# NusbioV2_Board.net
KiCad netlist of a schematic drawn in EAGLE
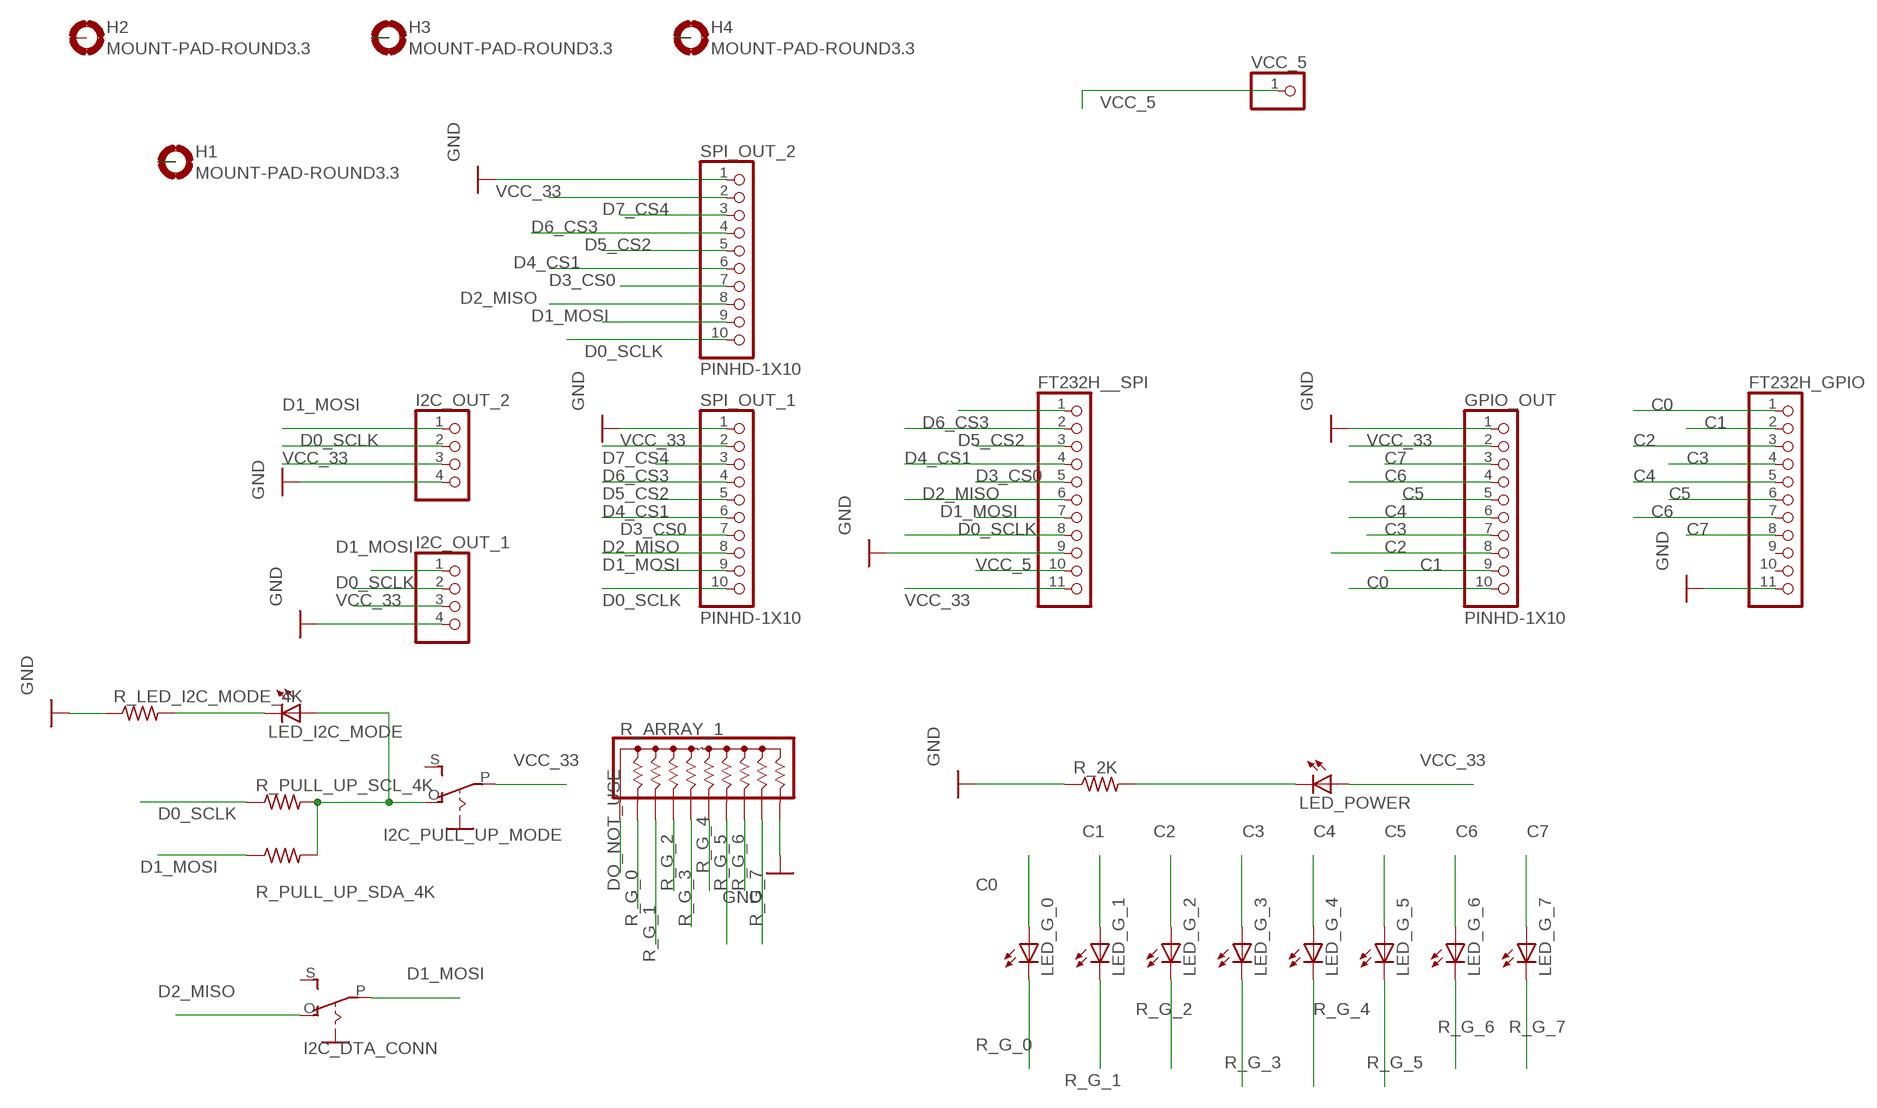
[diagram p0: schematic, sheet 1]

(export (version "E")
  (design (tool "Eeschema 10.0.6"))
  (components
    (comp (ref "FT232H_GPIO")
      (value "PINHD-1X11")
      (footprint "eagle-import:1X11")
      (libsource (lib "eagle-import") (part "PINHD-1X11"))
    )
    (comp (ref "FT232H__SPI")
      (value "PINHD-1X11")
      (footprint "eagle-import:1X11")
      (libsource (lib "eagle-import") (part "PINHD-1X11"))
    )
    (comp (ref "GPIO_OUT")
      (value "PINHD-1X10")
      (footprint "eagle-import:1X10-BIG")
      (libsource (lib "eagle-import") (part "PINHD-1X10"))
    )
    (comp (ref "H1")
      (value "MOUNT-PAD-ROUND3.3")
      (footprint "eagle-import:3,3-PAD")
      (libsource (lib "eagle-import") (part "MOUNT-PAD-ROUND3.3"))
    )
    (comp (ref "H2")
      (value "MOUNT-PAD-ROUND3.3")
      (footprint "eagle-import:3,3-PAD")
      (libsource (lib "eagle-import") (part "MOUNT-PAD-ROUND3.3"))
    )
    (comp (ref "H3")
      (value "MOUNT-PAD-ROUND3.3")
      (footprint "eagle-import:3,3-PAD")
      (libsource (lib "eagle-import") (part "MOUNT-PAD-ROUND3.3"))
    )
    (comp (ref "H4")
      (value "MOUNT-PAD-ROUND3.3")
      (footprint "eagle-import:3,3-PAD")
      (libsource (lib "eagle-import") (part "MOUNT-PAD-ROUND3.3"))
    )
    (comp (ref "I2C_DTA_CONN")
      (value "EG1218S")
      (footprint "eagle-import:EG1218")
      (libsource (lib "eagle-import") (part "EG1218S"))
    )
    (comp (ref "I2C_OUT_1")
      (value "PINHD-1X4")
      (footprint "eagle-import:1X04")
      (libsource (lib "eagle-import") (part "PINHD-1X4"))
    )
    (comp (ref "I2C_OUT_2")
      (value "PINHD-1X4")
      (footprint "eagle-import:1X04")
      (libsource (lib "eagle-import") (part "PINHD-1X4"))
    )
    (comp (ref "I2C_PULL_UP_MODE")
      (value "EG1218S")
      (footprint "eagle-import:EG1218")
      (libsource (lib "eagle-import") (part "EG1218S"))
    )
    (comp (ref "LED_G_0")
      (value "LEDSMT1206")
      (footprint "eagle-import:1206")
      (libsource (lib "eagle-import") (part "LEDSMT1206"))
    )
    (comp (ref "LED_G_1")
      (value "LEDSMT1206")
      (footprint "eagle-import:1206")
      (libsource (lib "eagle-import") (part "LEDSMT1206"))
    )
    (comp (ref "LED_G_2")
      (value "LEDSMT1206")
      (footprint "eagle-import:1206")
      (libsource (lib "eagle-import") (part "LEDSMT1206"))
    )
    (comp (ref "LED_G_3")
      (value "LEDSMT1206")
      (footprint "eagle-import:1206")
      (libsource (lib "eagle-import") (part "LEDSMT1206"))
    )
    (comp (ref "LED_G_4")
      (value "LEDSMT1206")
      (footprint "eagle-import:1206")
      (libsource (lib "eagle-import") (part "LEDSMT1206"))
    )
    (comp (ref "LED_G_5")
      (value "LEDSMT1206")
      (footprint "eagle-import:1206")
      (libsource (lib "eagle-import") (part "LEDSMT1206"))
    )
    (comp (ref "LED_G_6")
      (value "LEDSMT1206")
      (footprint "eagle-import:1206")
      (libsource (lib "eagle-import") (part "LEDSMT1206"))
    )
    (comp (ref "LED_G_7")
      (value "LEDSMT1206")
      (footprint "eagle-import:1206")
      (libsource (lib "eagle-import") (part "LEDSMT1206"))
    )
    (comp (ref "LED_I2C_MODE")
      (value "LEDSMT1206")
      (footprint "eagle-import:1206")
      (libsource (lib "eagle-import") (part "LEDSMT1206"))
    )
    (comp (ref "LED_POWER")
      (value "LEDSMT1206")
      (footprint "eagle-import:1206")
      (libsource (lib "eagle-import") (part "LEDSMT1206"))
    )
    (comp (ref "R_2K")
      (value "R-US_R1206")
      (footprint "eagle-import:R1206")
      (libsource (lib "eagle-import") (part "R-US_R1206"))
    )
    (comp (ref "R_ARRAY_1")
      (value "4610X")
      (footprint "eagle-import:SIP10")
      (libsource (lib "eagle-import") (part "4610X"))
    )
    (comp (ref "R_LED_I2C_MODE_4K")
      (value "R-US_R1206")
      (footprint "eagle-import:R1206")
      (libsource (lib "eagle-import") (part "R-US_R1206"))
    )
    (comp (ref "R_PULL_UP_SCL_4K")
      (value "R-US_R1206")
      (footprint "eagle-import:R1206")
      (libsource (lib "eagle-import") (part "R-US_R1206"))
    )
    (comp (ref "R_PULL_UP_SDA_4K")
      (value "R-US_R1206")
      (footprint "eagle-import:R1206")
      (libsource (lib "eagle-import") (part "R-US_R1206"))
    )
    (comp (ref "SPI_OUT_1")
      (value "PINHD-1X10")
      (footprint "eagle-import:1X10-BIG")
      (libsource (lib "eagle-import") (part "PINHD-1X10"))
    )
    (comp (ref "SPI_OUT_2")
      (value "PINHD-1X10")
      (footprint "eagle-import:1X10-BIG")
      (libsource (lib "eagle-import") (part "PINHD-1X10"))
    )
    (comp (ref "VCC_5")
      (value "PINHD-1X1")
      (footprint "eagle-import:1X01")
      (libsource (lib "eagle-import") (part "PINHD-1X1"))
    )
  )
  (nets
    (net (code "1") (name "/C0") (class "Default")
      (node (ref "FT232H_GPIO") (pin "1") (pinfunction "1_1") (pintype "passive"))
      (node (ref "GPIO_OUT") (pin "10") (pinfunction "10_10") (pintype "passive"))
      (node (ref "LED_G_0") (pin "A") (pinfunction "A_A") (pintype "passive"))
    )
    (net (code "2") (name "/C1") (class "Default")
      (node (ref "FT232H_GPIO") (pin "2") (pinfunction "2_2") (pintype "passive"))
      (node (ref "GPIO_OUT") (pin "9") (pinfunction "9_9") (pintype "passive"))
      (node (ref "LED_G_1") (pin "A") (pinfunction "A_A") (pintype "passive"))
    )
    (net (code "3") (name "/C2") (class "Default")
      (node (ref "FT232H_GPIO") (pin "3") (pinfunction "3_3") (pintype "passive"))
      (node (ref "GPIO_OUT") (pin "8") (pinfunction "8_8") (pintype "passive"))
      (node (ref "LED_G_2") (pin "A") (pinfunction "A_A") (pintype "passive"))
    )
    (net (code "4") (name "/C3") (class "Default")
      (node (ref "FT232H_GPIO") (pin "4") (pinfunction "4_4") (pintype "passive"))
      (node (ref "GPIO_OUT") (pin "7") (pinfunction "7_7") (pintype "passive"))
      (node (ref "LED_G_3") (pin "A") (pinfunction "A_A") (pintype "passive"))
    )
    (net (code "5") (name "/C4") (class "Default")
      (node (ref "FT232H_GPIO") (pin "5") (pinfunction "5_5") (pintype "passive"))
      (node (ref "GPIO_OUT") (pin "6") (pinfunction "6_6") (pintype "passive"))
      (node (ref "LED_G_4") (pin "A") (pinfunction "A_A") (pintype "passive"))
    )
    (net (code "6") (name "/C5") (class "Default")
      (node (ref "FT232H_GPIO") (pin "6") (pinfunction "6_6") (pintype "passive"))
      (node (ref "GPIO_OUT") (pin "5") (pinfunction "5_5") (pintype "passive"))
      (node (ref "LED_G_5") (pin "A") (pinfunction "A_A") (pintype "passive"))
    )
    (net (code "7") (name "/C6") (class "Default")
      (node (ref "FT232H_GPIO") (pin "7") (pinfunction "7_7") (pintype "passive"))
      (node (ref "GPIO_OUT") (pin "4") (pinfunction "4_4") (pintype "passive"))
      (node (ref "LED_G_6") (pin "A") (pinfunction "A_A") (pintype "passive"))
    )
    (net (code "8") (name "/C7") (class "Default")
      (node (ref "FT232H_GPIO") (pin "8") (pinfunction "8_8") (pintype "passive"))
      (node (ref "GPIO_OUT") (pin "3") (pinfunction "3_3") (pintype "passive"))
      (node (ref "LED_G_7") (pin "A") (pinfunction "A_A") (pintype "passive"))
    )
    (net (code "9") (name "/D0_SCLK") (class "Default")
      (node (ref "FT232H__SPI") (pin "8") (pinfunction "8_8") (pintype "passive"))
      (node (ref "I2C_OUT_1") (pin "2") (pinfunction "2_2") (pintype "passive"))
      (node (ref "I2C_OUT_2") (pin "2") (pinfunction "2_2") (pintype "passive"))
      (node (ref "R_PULL_UP_SCL_4K") (pin "1") (pinfunction "1_1") (pintype "passive"))
      (node (ref "SPI_OUT_1") (pin "10") (pinfunction "10_10") (pintype "passive"))
      (node (ref "SPI_OUT_2") (pin "10") (pinfunction "10_10") (pintype "passive"))
    )
    (net (code "10") (name "/D1_MOSI") (class "Default")
      (node (ref "FT232H__SPI") (pin "7") (pinfunction "7_7") (pintype "passive"))
      (node (ref "I2C_DTA_CONN") (pin "P") (pinfunction "P_P") (pintype "passive"))
      (node (ref "I2C_OUT_1") (pin "1") (pinfunction "1_1") (pintype "passive"))
      (node (ref "I2C_OUT_2") (pin "1") (pinfunction "1_1") (pintype "passive"))
      (node (ref "R_PULL_UP_SDA_4K") (pin "1") (pinfunction "1_1") (pintype "passive"))
      (node (ref "SPI_OUT_1") (pin "9") (pinfunction "9_9") (pintype "passive"))
      (node (ref "SPI_OUT_2") (pin "9") (pinfunction "9_9") (pintype "passive"))
    )
    (net (code "11") (name "/D2_MISO") (class "Default")
      (node (ref "FT232H__SPI") (pin "6") (pinfunction "6_6") (pintype "passive"))
      (node (ref "I2C_DTA_CONN") (pin "O") (pinfunction "O_O") (pintype "passive"))
      (node (ref "SPI_OUT_1") (pin "8") (pinfunction "8_8") (pintype "passive"))
      (node (ref "SPI_OUT_2") (pin "8") (pinfunction "8_8") (pintype "passive"))
    )
    (net (code "12") (name "/D3_CS0") (class "Default")
      (node (ref "FT232H__SPI") (pin "5") (pinfunction "5_5") (pintype "passive"))
      (node (ref "SPI_OUT_1") (pin "7") (pinfunction "7_7") (pintype "passive"))
      (node (ref "SPI_OUT_2") (pin "7") (pinfunction "7_7") (pintype "passive"))
    )
    (net (code "13") (name "/D4_CS1") (class "Default")
      (node (ref "FT232H__SPI") (pin "4") (pinfunction "4_4") (pintype "passive"))
      (node (ref "SPI_OUT_1") (pin "6") (pinfunction "6_6") (pintype "passive"))
      (node (ref "SPI_OUT_2") (pin "6") (pinfunction "6_6") (pintype "passive"))
    )
    (net (code "14") (name "/D5_CS2") (class "Default")
      (node (ref "FT232H__SPI") (pin "3") (pinfunction "3_3") (pintype "passive"))
      (node (ref "SPI_OUT_1") (pin "5") (pinfunction "5_5") (pintype "passive"))
      (node (ref "SPI_OUT_2") (pin "5") (pinfunction "5_5") (pintype "passive"))
    )
    (net (code "15") (name "/D6_CS3") (class "Default")
      (node (ref "FT232H__SPI") (pin "2") (pinfunction "2_2") (pintype "passive"))
      (node (ref "SPI_OUT_1") (pin "4") (pinfunction "4_4") (pintype "passive"))
      (node (ref "SPI_OUT_2") (pin "4") (pinfunction "4_4") (pintype "passive"))
    )
    (net (code "16") (name "/D7_CS4") (class "Default")
      (node (ref "FT232H__SPI") (pin "1") (pinfunction "1_1") (pintype "passive"))
      (node (ref "SPI_OUT_1") (pin "3") (pinfunction "3_3") (pintype "passive"))
      (node (ref "SPI_OUT_2") (pin "3") (pinfunction "3_3") (pintype "passive"))
    )
    (net (code "17") (name "/DO_NOT_USE") (class "Default")
      (node (ref "R_ARRAY_1") (pin "1") (pinfunction "1_1") (pintype "passive"))
    )
    (net (code "18") (name "/R_G_0") (class "Default")
      (node (ref "LED_G_0") (pin "C") (pinfunction "C_C") (pintype "passive"))
      (node (ref "R_ARRAY_1") (pin "2") (pinfunction "2_2") (pintype "passive"))
    )
    (net (code "19") (name "/R_G_1") (class "Default")
      (node (ref "LED_G_1") (pin "C") (pinfunction "C_C") (pintype "passive"))
      (node (ref "R_ARRAY_1") (pin "3") (pinfunction "3_3") (pintype "passive"))
    )
    (net (code "20") (name "/R_G_2") (class "Default")
      (node (ref "LED_G_2") (pin "C") (pinfunction "C_C") (pintype "passive"))
      (node (ref "R_ARRAY_1") (pin "4") (pinfunction "4_4") (pintype "passive"))
    )
    (net (code "21") (name "/R_G_3") (class "Default")
      (node (ref "LED_G_3") (pin "C") (pinfunction "C_C") (pintype "passive"))
      (node (ref "R_ARRAY_1") (pin "5") (pinfunction "5_5") (pintype "passive"))
    )
    (net (code "22") (name "/R_G_4") (class "Default")
      (node (ref "LED_G_4") (pin "C") (pinfunction "C_C") (pintype "passive"))
      (node (ref "R_ARRAY_1") (pin "6") (pinfunction "6_6") (pintype "passive"))
    )
    (net (code "23") (name "/R_G_5") (class "Default")
      (node (ref "LED_G_5") (pin "C") (pinfunction "C_C") (pintype "passive"))
      (node (ref "R_ARRAY_1") (pin "7") (pinfunction "7_7") (pintype "passive"))
    )
    (net (code "24") (name "/R_G_6") (class "Default")
      (node (ref "LED_G_6") (pin "C") (pinfunction "C_C") (pintype "passive"))
      (node (ref "R_ARRAY_1") (pin "8") (pinfunction "8_8") (pintype "passive"))
    )
    (net (code "25") (name "/R_G_7") (class "Default")
      (node (ref "LED_G_7") (pin "C") (pinfunction "C_C") (pintype "passive"))
      (node (ref "R_ARRAY_1") (pin "9") (pinfunction "9_9") (pintype "passive"))
    )
    (net (code "26") (name "/VCC_5") (class "Default")
      (node (ref "FT232H__SPI") (pin "10") (pinfunction "10_10") (pintype "passive"))
      (node (ref "VCC_5") (pin "1") (pinfunction "1_1") (pintype "passive"))
    )
    (net (code "27") (name "/VCC_33") (class "Default")
      (node (ref "FT232H__SPI") (pin "11") (pinfunction "11_11") (pintype "passive"))
      (node (ref "GPIO_OUT") (pin "2") (pinfunction "2_2") (pintype "passive"))
      (node (ref "I2C_OUT_1") (pin "3") (pinfunction "3_3") (pintype "passive"))
      (node (ref "I2C_OUT_2") (pin "3") (pinfunction "3_3") (pintype "passive"))
      (node (ref "I2C_PULL_UP_MODE") (pin "P") (pinfunction "P_P") (pintype "passive"))
      (node (ref "LED_POWER") (pin "A") (pinfunction "A_A") (pintype "passive"))
      (node (ref "SPI_OUT_1") (pin "2") (pinfunction "2_2") (pintype "passive"))
      (node (ref "SPI_OUT_2") (pin "2") (pinfunction "2_2") (pintype "passive"))
    )
    (net (code "28") (name "GND") (class "Default")
      (node (ref "FT232H_GPIO") (pin "11") (pinfunction "11_11") (pintype "passive"))
      (node (ref "FT232H__SPI") (pin "9") (pinfunction "9_9") (pintype "passive"))
      (node (ref "GPIO_OUT") (pin "1") (pinfunction "1_1") (pintype "passive"))
      (node (ref "I2C_OUT_1") (pin "4") (pinfunction "4_4") (pintype "passive"))
      (node (ref "I2C_OUT_2") (pin "4") (pinfunction "4_4") (pintype "passive"))
      (node (ref "R_2K") (pin "1") (pinfunction "1_1") (pintype "passive"))
      (node (ref "R_ARRAY_1") (pin "10") (pinfunction "10_10") (pintype "passive"))
      (node (ref "R_LED_I2C_MODE_4K") (pin "1") (pinfunction "1_1") (pintype "passive"))
      (node (ref "SPI_OUT_1") (pin "1") (pinfunction "1_1") (pintype "passive"))
      (node (ref "SPI_OUT_2") (pin "1") (pinfunction "1_1") (pintype "passive"))
    )
    (net (code "29") (name "Net-(I2C_PULL_UP_MODE-PadO)") (class "Default")
      (node (ref "I2C_PULL_UP_MODE") (pin "O") (pinfunction "O_O") (pintype "passive"))
      (node (ref "LED_I2C_MODE") (pin "A") (pinfunction "A_A") (pintype "passive"))
      (node (ref "R_PULL_UP_SCL_4K") (pin "2") (pinfunction "2_2") (pintype "passive"))
      (node (ref "R_PULL_UP_SDA_4K") (pin "2") (pinfunction "2_2") (pintype "passive"))
    )
    (net (code "30") (name "Net-(LED_I2C_MODE-PadC)") (class "Default")
      (node (ref "LED_I2C_MODE") (pin "C") (pinfunction "C_C") (pintype "passive"))
      (node (ref "R_LED_I2C_MODE_4K") (pin "2") (pinfunction "2_2") (pintype "passive"))
    )
    (net (code "31") (name "Net-(LED_POWER-PadC)") (class "Default")
      (node (ref "LED_POWER") (pin "C") (pinfunction "C_C") (pintype "passive"))
      (node (ref "R_2K") (pin "2") (pinfunction "2_2") (pintype "passive"))
    )
    (net (code "32") (name "unconnected-(FT232H_GPIO-Pad9)") (class "Default")
      (node (ref "FT232H_GPIO") (pin "9") (pinfunction "9_9") (pintype "passive"))
    )
    (net (code "33") (name "unconnected-(FT232H_GPIO-Pad10)") (class "Default")
      (node (ref "FT232H_GPIO") (pin "10") (pinfunction "10_10") (pintype "passive"))
    )
    (net (code "34") (name "unconnected-(H1-MOUNT-PadB3,3)") (class "Default")
      (node (ref "H1") (pin "B3,3") (pinfunction "MOUNT_B3,3") (pintype "passive"))
    )
    (net (code "35") (name "unconnected-(H2-MOUNT-PadB3,3)") (class "Default")
      (node (ref "H2") (pin "B3,3") (pinfunction "MOUNT_B3,3") (pintype "passive"))
    )
    (net (code "36") (name "unconnected-(H3-MOUNT-PadB3,3)") (class "Default")
      (node (ref "H3") (pin "B3,3") (pinfunction "MOUNT_B3,3") (pintype "passive"))
    )
    (net (code "37") (name "unconnected-(H4-MOUNT-PadB3,3)") (class "Default")
      (node (ref "H4") (pin "B3,3") (pinfunction "MOUNT_B3,3") (pintype "passive"))
    )
    (net (code "38") (name "unconnected-(I2C_DTA_CONN-PadS)") (class "Default")
      (node (ref "I2C_DTA_CONN") (pin "S") (pinfunction "S_S") (pintype "passive"))
    )
    (net (code "39") (name "unconnected-(I2C_PULL_UP_MODE-PadS)") (class "Default")
      (node (ref "I2C_PULL_UP_MODE") (pin "S") (pinfunction "S_S") (pintype "passive"))
    )
  )
)
